# driver-ha-v4.net
KiCad netlist of a schematic drawn in EAGLE
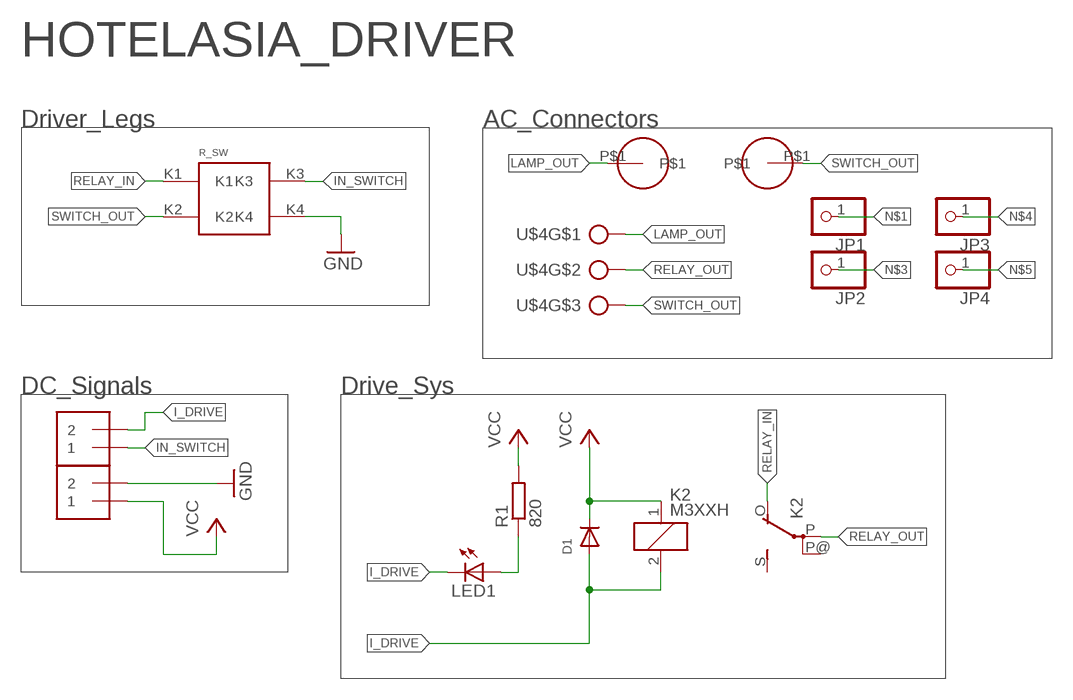
[diagram p0: schematic, sheet 1]

(export (version "E")
  (design (tool "Eeschema 10.0.6"))
  (components
    (comp (ref "D1")
      (value "DIODESMA")
      (footprint "eagle-import:SMADIODE")
      (libsource (lib "eagle-import") (part "DIODESMA"))
    )
    (comp (ref "J1")
      (value "1X2-3.5MM")
      (footprint "eagle-import:1X2-3.5MM")
      (libsource (lib "eagle-import") (part "1X2-3.5MM"))
    )
    (comp (ref "J2")
      (value "1X2-3.5MM")
      (footprint "eagle-import:1X2-3.5MM")
      (libsource (lib "eagle-import") (part "1X2-3.5MM"))
    )
    (comp (ref "JP1")
      (value "PINHD-1X1")
      (footprint "eagle-import:1X01")
      (libsource (lib "eagle-import") (part "PINHD-1X1"))
    )
    (comp (ref "JP2")
      (value "PINHD-1X1")
      (footprint "eagle-import:1X01")
      (libsource (lib "eagle-import") (part "PINHD-1X1"))
    )
    (comp (ref "JP3")
      (value "PINHD-1X1")
      (footprint "eagle-import:1X01")
      (libsource (lib "eagle-import") (part "PINHD-1X1"))
    )
    (comp (ref "JP4")
      (value "PINHD-1X1")
      (footprint "eagle-import:1X01")
      (libsource (lib "eagle-import") (part "PINHD-1X1"))
    )
    (comp (ref "K2")
      (value "M3XXH")
      (footprint "eagle-import:M3XXH")
      (libsource (lib "eagle-import") (part "M3XXH"))
    )
    (comp (ref "LED1")
      (value "LEDCHIPLED_0805")
      (footprint "eagle-import:CHIPLED_0805")
      (libsource (lib "eagle-import") (part "LEDCHIPLED_0805"))
    )
    (comp (ref "PAD1")
      (value "ROOM_SWITCH")
      (footprint "eagle-import:ROOM_SWITCH")
      (libsource (lib "eagle-import") (part "ROOM_SWITCH"))
    )
    (comp (ref "R1")
      (value "820")
      (footprint "eagle-import:R0805")
      (libsource (lib "eagle-import") (part "R-EU_R0805"))
    )
    (comp (ref "U$1")
      (value "CONN-CABLE")
      (footprint "eagle-import:CONN-CABLE")
      (libsource (lib "eagle-import") (part "CONN-CABLE"))
    )
    (comp (ref "U$3")
      (value "CONN-CABLE")
      (footprint "eagle-import:CONN-CABLE")
      (libsource (lib "eagle-import") (part "CONN-CABLE"))
    )
    (comp (ref "U$4")
      (value "AK3003")
      (footprint "eagle-import:AK3003")
      (libsource (lib "eagle-import") (part "AK3003"))
    )
  )
  (nets
    (net (code "1") (name "GND") (class "Default")
      (node (ref "J2") (pin "2") (pinfunction "2_2") (pintype "passive"))
      (node (ref "PAD1") (pin "K4") (pinfunction "K4_K4") (pintype "bidirectional"))
    )
    (net (code "2") (name "IN_SWITCH") (class "Default")
      (node (ref "J1") (pin "1") (pinfunction "1_1") (pintype "passive"))
      (node (ref "PAD1") (pin "K3") (pinfunction "K3_K3") (pintype "bidirectional"))
    )
    (net (code "3") (name "I_DRIVE") (class "Default")
      (node (ref "D1") (pin "A") (pinfunction "A_A") (pintype "passive"))
      (node (ref "J1") (pin "2") (pinfunction "2_2") (pintype "passive"))
      (node (ref "K2") (pin "2") (pinfunction "2_2") (pintype "passive"))
      (node (ref "LED1") (pin "C") (pinfunction "C_C") (pintype "passive"))
    )
    (net (code "4") (name "LAMP_OUT") (class "Default")
      (node (ref "U$1") (pin "P$1") (pinfunction "P$1_P$1") (pintype "bidirectional"))
      (node (ref "U$4") (pin "1") (pinfunction "KL_1") (pintype "passive"))
    )
    (net (code "5") (name "N$1") (class "Default")
      (node (ref "JP1") (pin "1") (pinfunction "1_1") (pintype "passive"))
    )
    (net (code "6") (name "N$3") (class "Default")
      (node (ref "JP2") (pin "1") (pinfunction "1_1") (pintype "passive"))
    )
    (net (code "7") (name "N$4") (class "Default")
      (node (ref "JP3") (pin "1") (pinfunction "1_1") (pintype "passive"))
    )
    (net (code "8") (name "N$5") (class "Default")
      (node (ref "JP4") (pin "1") (pinfunction "1_1") (pintype "passive"))
    )
    (net (code "9") (name "Net-(LED1-PadA)") (class "Default")
      (node (ref "LED1") (pin "A") (pinfunction "A_A") (pintype "passive"))
      (node (ref "R1") (pin "1") (pinfunction "1_1") (pintype "passive"))
    )
    (net (code "10") (name "RELAY_IN") (class "Default")
      (node (ref "K2") (pin "O") (pinfunction "O_O") (pintype "passive"))
      (node (ref "PAD1") (pin "K1") (pinfunction "K1_K1") (pintype "bidirectional"))
    )
    (net (code "11") (name "RELAY_OUT") (class "Default")
      (node (ref "K2") (pin "P") (pinfunction "P_P") (pintype "passive"))
      (node (ref "U$4") (pin "2") (pinfunction "KL_2") (pintype "passive"))
    )
    (net (code "12") (name "SWITCH_OUT") (class "Default")
      (node (ref "PAD1") (pin "K2") (pinfunction "K2_K2") (pintype "bidirectional"))
      (node (ref "U$3") (pin "P$1") (pinfunction "P$1_P$1") (pintype "bidirectional"))
      (node (ref "U$4") (pin "3") (pinfunction "KL_3") (pintype "passive"))
    )
    (net (code "13") (name "VCC") (class "Default")
      (node (ref "D1") (pin "C") (pinfunction "C_C") (pintype "passive"))
      (node (ref "J2") (pin "1") (pinfunction "1_1") (pintype "passive"))
      (node (ref "K2") (pin "1") (pinfunction "1_1") (pintype "passive"))
      (node (ref "R1") (pin "2") (pinfunction "2_2") (pintype "passive"))
    )
    (net (code "14") (name "unconnected-(K2-PadS)") (class "Default")
      (node (ref "K2") (pin "S") (pinfunction "S_S") (pintype "passive"))
    )
    (net (code "15") (name "unconnected-(K2B-P-PadP@)") (class "Default")
      (node (ref "K2") (pin "P@") (pinfunction "P_P@") (pintype "passive"))
    )
  )
)
